# AlertesLocales.net
KiCad netlist of a schematic drawn in Altium Designer
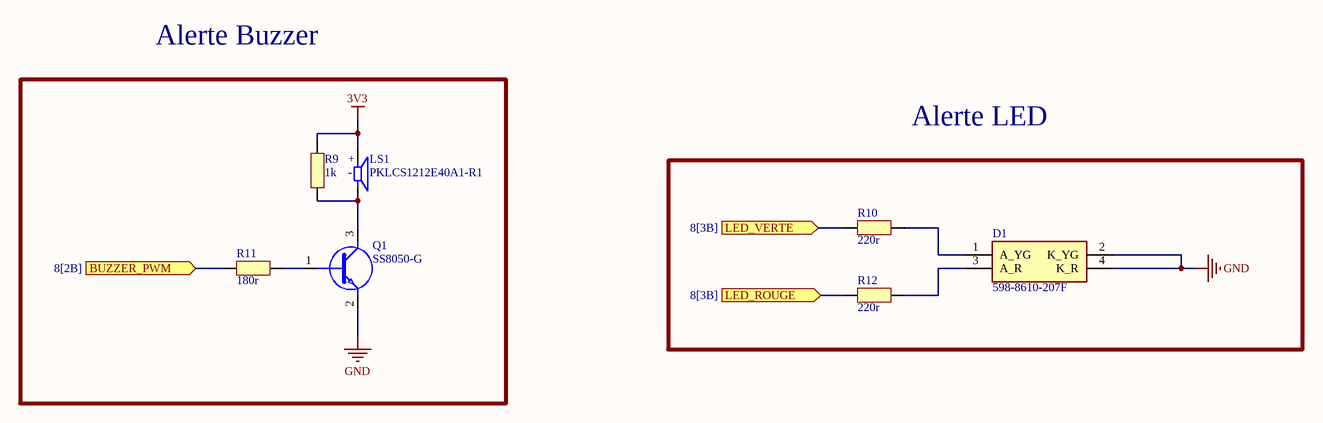
[diagram p0: AlertesLocales.SchDoc]

(export (version "E")
  (design (tool "Eeschema 10.0.6"))
  (components
    (comp (ref "D1")
      (value "598-8610-207F")
      (footprint "5988610207F")
      (description "Standard LEDs - SMD Red/Green WC 80/50mcd 645/570nm")
      (fields (field (name "MOUSER PART NUMBER") "645-598-8610-207F"))
      (libsource (lib "SCHLibrary") (part "598-8610-207F"))
    )
    (comp (ref "LS1")
      (value "PKLCS1212E40A1-R1")
      (footprint "SPKR_PKLCS1212E40A1-R1")
      (description "Buzzers Transducer, Externally Driven Piezo 1.5V 2kHz 70dB @ 1.5V, 10cm Surface Mount Solder Pads")
      (fields (field (name "MF") "Murata Electronics"))
      (libsource (lib "SCHLibrary") (part "PKLCS1212E40A1-R1"))
    )
    (comp (ref "Q1")
      (value "SS8050-G")
      (footprint "SS8050-G")
      (description "Bipolar Transistors - BJT NPN TRANSISTOR 1.5A 40V")
      (libsource (lib "SCHLibrary") (part "SS8050-G"))
    )
    (comp (ref "R9") (value "1k") (footprint "RESC1005X06N") (libsource (lib "") (part "Resistor_1")))
    (comp (ref "R10")
      (value "220r")
      (footprint "RESC1005X06N")
      (libsource (lib "SCHLibrary") (part "Resistor"))
    )
    (comp (ref "R11")
      (value "180r")
      (footprint "RESC1005X06N")
      (libsource (lib "SCHLibrary") (part "Resistor"))
    )
    (comp (ref "R12")
      (value "220r")
      (footprint "RESC1005X06N")
      (libsource (lib "SCHLibrary") (part "Resistor"))
    )
  )
  (nets
    (net (code "1") (name "/BUZZER_PWM") (class "Default")
      (node (ref "R11") (pin "1") (pinfunction "1_1") (pintype "passive"))
    )
    (net (code "2") (name "/LED_ROUGE") (class "Default")
      (node (ref "R12") (pin "1") (pinfunction "1_1") (pintype "passive"))
    )
    (net (code "3") (name "/LED_VERTE") (class "Default")
      (node (ref "R10") (pin "1") (pinfunction "1_1") (pintype "passive"))
    )
    (net (code "4") (name "3V3") (class "Default")
      (node (ref "LS1") (pin "P") (pinfunction "P_P") (pintype "passive"))
      (node (ref "R9") (pin "2") (pinfunction "2_2") (pintype "passive"))
    )
    (net (code "5") (name "GND") (class "Default")
      (node (ref "D1") (pin "2") (pinfunction "K_YG_2") (pintype "passive"))
      (node (ref "D1") (pin "4") (pinfunction "K_R_4") (pintype "passive"))
      (node (ref "Q1") (pin "2") (pinfunction "E_2") (pintype "passive"))
    )
    (net (code "6") (name "Net-(D1-A_R)") (class "Default")
      (node (ref "D1") (pin "3") (pinfunction "A_R_3") (pintype "passive"))
      (node (ref "R12") (pin "2") (pinfunction "2_2") (pintype "passive"))
    )
    (net (code "7") (name "Net-(D1-A_YG)") (class "Default")
      (node (ref "D1") (pin "1") (pinfunction "A_YG_1") (pintype "passive"))
      (node (ref "R10") (pin "2") (pinfunction "2_2") (pintype "passive"))
    )
    (net (code "8") (name "Net-(Q1-B)") (class "Default")
      (node (ref "Q1") (pin "1") (pinfunction "B_1") (pintype "passive"))
      (node (ref "R11") (pin "2") (pinfunction "2_2") (pintype "passive"))
    )
    (net (code "9") (name "Net-(Q1-C)") (class "Default")
      (node (ref "LS1") (pin "N") (pinfunction "N_N") (pintype "passive"))
      (node (ref "Q1") (pin "3") (pinfunction "C_3") (pintype "passive"))
      (node (ref "R9") (pin "1") (pinfunction "1_1") (pintype "passive"))
    )
  )
)
